# STM32F4Stick.net
KiCad netlist of a schematic drawn in EAGLE
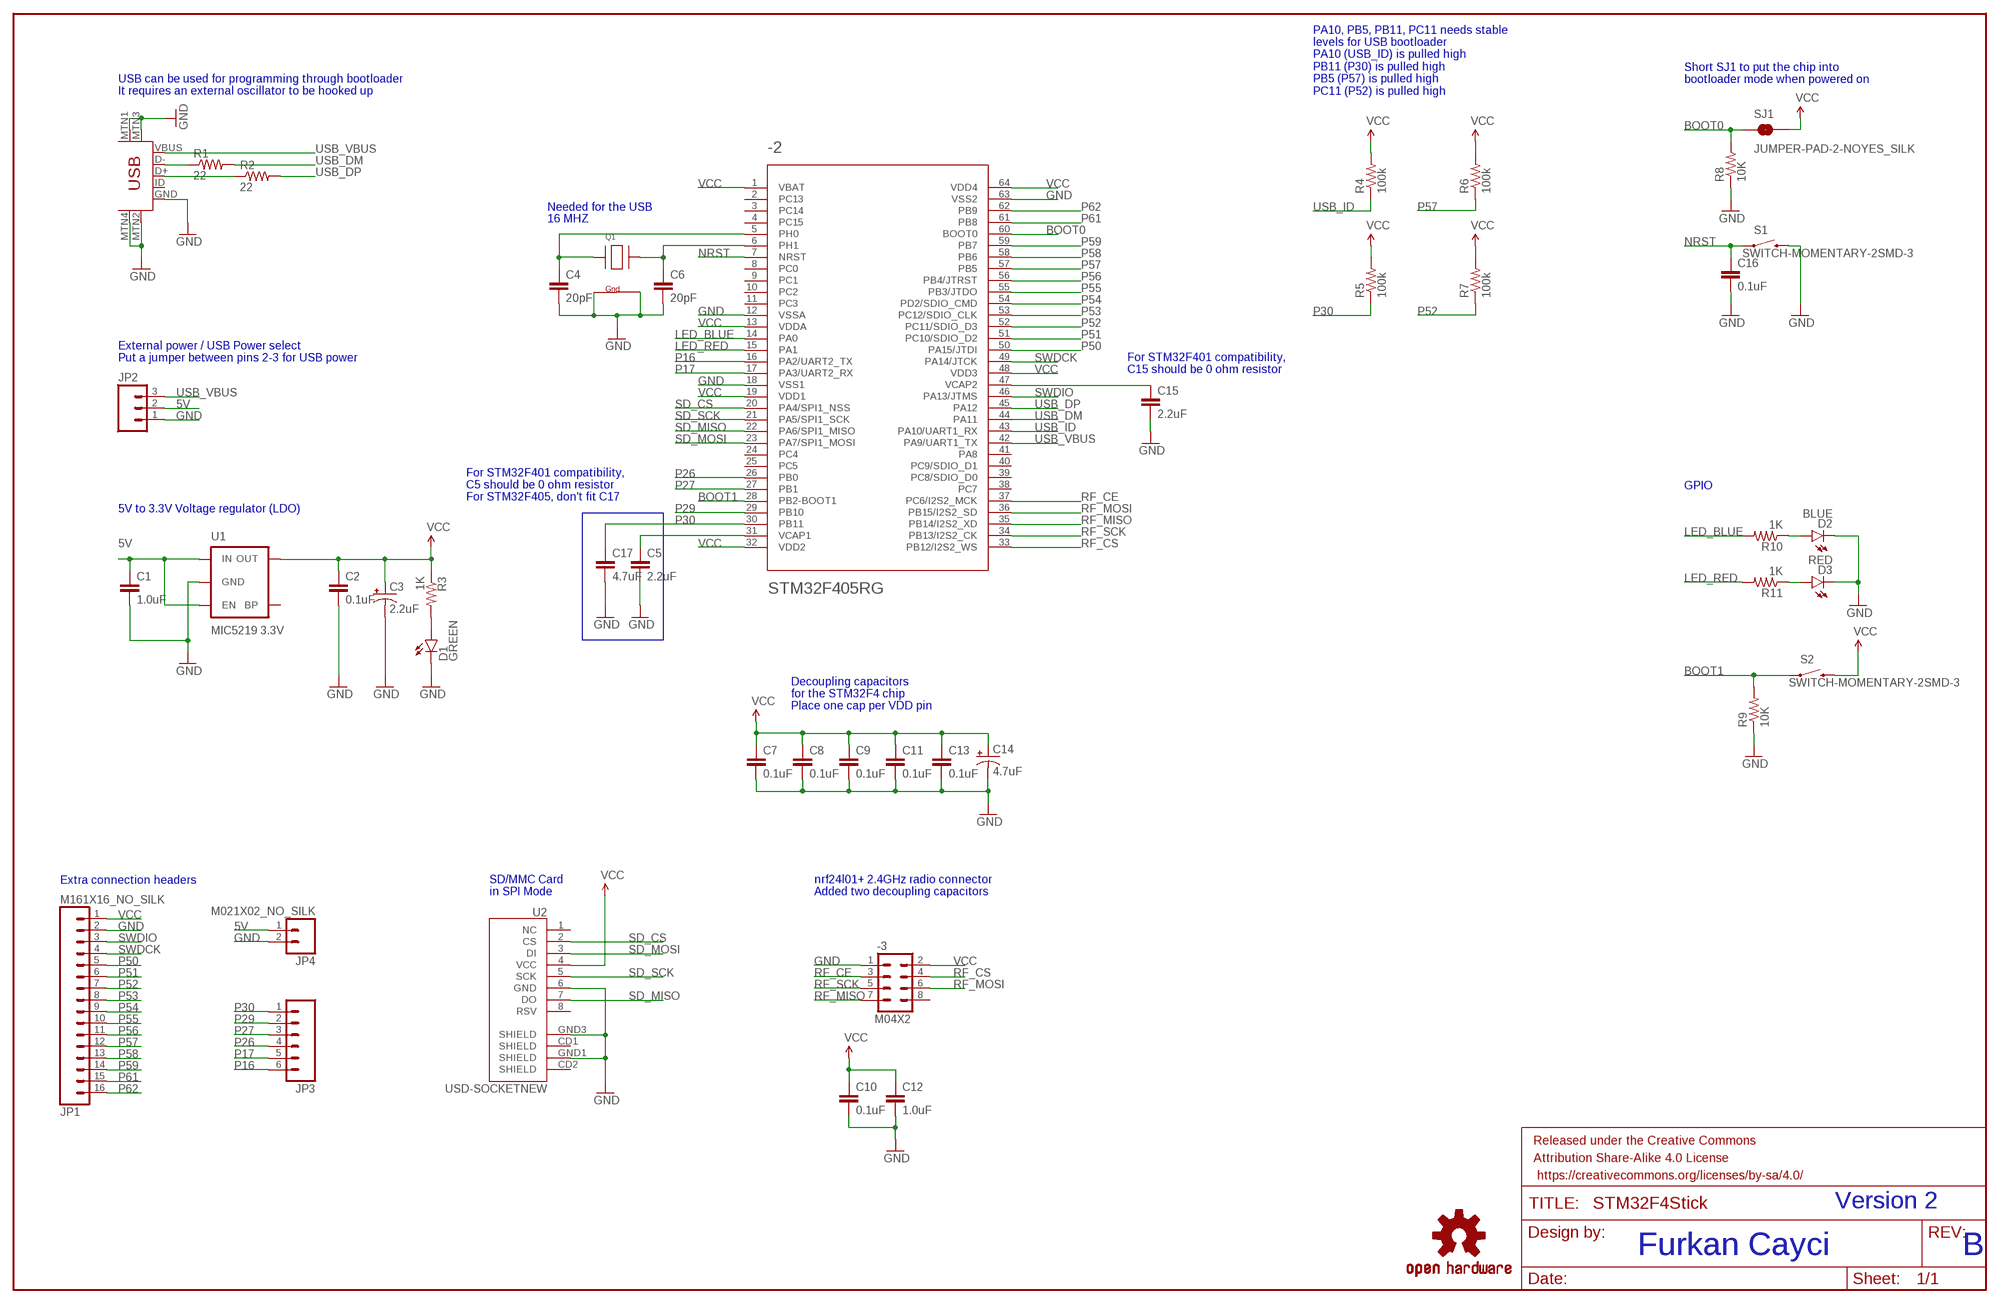
[diagram p0: schematic, sheet 1]

(export (version "E")
  (design (tool "Eeschema 10.0.6"))
  (components
    (comp (ref "-1")
      (value "USB-MINIB-5PIN")
      (footprint "eagle-import:USB-MINIB")
      (libsource (lib "eagle-import") (part "USB-MINIB-5PIN"))
    )
    (comp (ref "-2")
      (value "STM32F405RG")
      (footprint "eagle-import:TQFP64")
      (libsource (lib "eagle-import") (part "STM32F405RG"))
    )
    (comp (ref "-3")
      (value "M04X2")
      (footprint "eagle-import:2X4")
      (libsource (lib "eagle-import") (part "M04X2"))
    )
    (comp (ref "C1")
      (value "1.0uF")
      (footprint "eagle-import:0603-CAP")
      (libsource (lib "eagle-import") (part "1.0UF-16V-10%(0603)"))
    )
    (comp (ref "C2")
      (value "0.1uF")
      (footprint "eagle-import:0603-CAP")
      (libsource (lib "eagle-import") (part "0.1UF-25V-5%(0603)"))
    )
    (comp (ref "C3")
      (value "2.2uF")
      (footprint "eagle-import:EIA3216")
      (libsource (lib "eagle-import") (part "CAP_POL1206"))
    )
    (comp (ref "C4")
      (value "20pF")
      (footprint "eagle-import:0603-CAP")
      (libsource (lib "eagle-import") (part "12PF-50V-5%(0603)"))
    )
    (comp (ref "C5")
      (value "2.2uF")
      (footprint "eagle-import:0603-CAP")
      (libsource (lib "eagle-import") (part "2.2UF-10V-20%(0603)"))
    )
    (comp (ref "C6")
      (value "20pF")
      (footprint "eagle-import:0603-CAP")
      (libsource (lib "eagle-import") (part "12PF-50V-5%(0603)"))
    )
    (comp (ref "C7")
      (value "0.1uF")
      (footprint "eagle-import:0603-CAP")
      (libsource (lib "eagle-import") (part "0.1UF-25V-5%(0603)"))
    )
    (comp (ref "C8")
      (value "0.1uF")
      (footprint "eagle-import:0603-CAP")
      (libsource (lib "eagle-import") (part "0.1UF-25V-5%(0603)"))
    )
    (comp (ref "C9")
      (value "0.1uF")
      (footprint "eagle-import:0603-CAP")
      (libsource (lib "eagle-import") (part "0.1UF-25V-5%(0603)"))
    )
    (comp (ref "C10")
      (value "0.1uF")
      (footprint "eagle-import:0603-CAP")
      (libsource (lib "eagle-import") (part "0.1UF-25V-5%(0603)"))
    )
    (comp (ref "C11")
      (value "0.1uF")
      (footprint "eagle-import:0603-CAP")
      (libsource (lib "eagle-import") (part "0.1UF-25V-5%(0603)"))
    )
    (comp (ref "C12")
      (value "1.0uF")
      (footprint "eagle-import:0603-CAP")
      (libsource (lib "eagle-import") (part "1.0UF-16V-10%(0603)"))
    )
    (comp (ref "C13")
      (value "0.1uF")
      (footprint "eagle-import:0603-CAP")
      (libsource (lib "eagle-import") (part "0.1UF-25V-5%(0603)"))
    )
    (comp (ref "C14")
      (value "4.7uF")
      (footprint "eagle-import:EIA3216")
      (libsource (lib "eagle-import") (part "CAP_POL1206"))
    )
    (comp (ref "C15")
      (value "2.2uF")
      (footprint "eagle-import:0603-CAP")
      (libsource (lib "eagle-import") (part "2.2UF-10V-20%(0603)"))
    )
    (comp (ref "C16")
      (value "0.1uF")
      (footprint "eagle-import:0603-CAP")
      (libsource (lib "eagle-import") (part "0.1UF-25V-5%(0603)"))
    )
    (comp (ref "C17")
      (value "4.7uF")
      (footprint "eagle-import:0603-CAP")
      (libsource (lib "eagle-import") (part "4.7UF-6.3V-10%(0603)0603"))
    )
    (comp (ref "D1")
      (value "GREEN")
      (footprint "eagle-import:LED-0603")
      (libsource (lib "eagle-import") (part "LED-GREEN0603"))
    )
    (comp (ref "D2")
      (value "BLUE")
      (footprint "eagle-import:LED-0603")
      (libsource (lib "eagle-import") (part "LED-BLUE0603"))
    )
    (comp (ref "D3")
      (value "RED")
      (footprint "eagle-import:LED-0603")
      (libsource (lib "eagle-import") (part "LED-RED0603"))
    )
    (comp (ref "FRAME1")
      (value "FRAME-LEDGER")
      (footprint "eagle-import:CREATIVE_COMMONS")
      (libsource (lib "eagle-import") (part "FRAME-LEDGER"))
    )
    (comp (ref "JP1")
      (value "M161X16_NO_SILK")
      (footprint "eagle-import:1X16_NO_SILK")
      (libsource (lib "eagle-import") (part "M161X16_NO_SILK"))
    )
    (comp (ref "JP2")
      (value "M031X03_NO_SILK")
      (footprint "eagle-import:1X03_NO_SILK")
      (libsource (lib "eagle-import") (part "M031X03_NO_SILK"))
    )
    (comp (ref "JP3")
      (value "M06NO_SILK")
      (footprint "eagle-import:1X06_NO_SILK")
      (libsource (lib "eagle-import") (part "M06NO_SILK"))
    )
    (comp (ref "JP4")
      (value "M021X02_NO_SILK")
      (footprint "eagle-import:1X02_NO_SILK")
      (libsource (lib "eagle-import") (part "M021X02_NO_SILK"))
    )
    (comp (ref "LOGO1")
      (value "OSHW-LOGOM")
      (footprint "eagle-import:OSHW-LOGO-M")
      (libsource (lib "eagle-import") (part "OSHW-LOGOM"))
    )
    (comp (ref "Q1")
      (value "XTAL-4-3225")
      (footprint "eagle-import:NX3225")
      (libsource (lib "eagle-import") (part "XTAL-4-3225"))
    )
    (comp (ref "R1")
      (value "22")
      (footprint "eagle-import:0603-RES")
      (libsource (lib "eagle-import") (part "22OHM1/10W1%(0603)"))
    )
    (comp (ref "R2")
      (value "22")
      (footprint "eagle-import:0603-RES")
      (libsource (lib "eagle-import") (part "22OHM1/10W1%(0603)"))
    )
    (comp (ref "R3")
      (value "1K")
      (footprint "eagle-import:0603-RES")
      (libsource (lib "eagle-import") (part "1KOHM1/10W1%(0603)"))
    )
    (comp (ref "R4")
      (value "100k")
      (footprint "eagle-import:0603-RES")
      (libsource (lib "eagle-import") (part "100KOHM1/10W1%(0603)"))
    )
    (comp (ref "R5")
      (value "100k")
      (footprint "eagle-import:0603-RES")
      (libsource (lib "eagle-import") (part "100KOHM1/10W1%(0603)"))
    )
    (comp (ref "R6")
      (value "100k")
      (footprint "eagle-import:0603-RES")
      (libsource (lib "eagle-import") (part "100KOHM1/10W1%(0603)"))
    )
    (comp (ref "R7")
      (value "100k")
      (footprint "eagle-import:0603-RES")
      (libsource (lib "eagle-import") (part "100KOHM1/10W1%(0603)"))
    )
    (comp (ref "R8")
      (value "10K")
      (footprint "eagle-import:0603-RES")
      (libsource (lib "eagle-import") (part "10KOHM1/10W1%(0603)0603"))
    )
    (comp (ref "R9")
      (value "10K")
      (footprint "eagle-import:0603-RES")
      (libsource (lib "eagle-import") (part "10KOHM1/10W1%(0603)0603"))
    )
    (comp (ref "R10")
      (value "1K")
      (footprint "eagle-import:0603-RES")
      (libsource (lib "eagle-import") (part "1KOHM1/10W1%(0603)"))
    )
    (comp (ref "R11")
      (value "1K")
      (footprint "eagle-import:0603-RES")
      (libsource (lib "eagle-import") (part "1KOHM1/10W1%(0603)"))
    )
    (comp (ref "S1")
      (value "SWITCH-MOMENTARY-2SMD-3")
      (footprint "eagle-import:TACTILE_SWITCH_SMD-3")
      (libsource (lib "eagle-import") (part "SWITCH-MOMENTARY-2SMD-3"))
    )
    (comp (ref "S2")
      (value "SWITCH-MOMENTARY-2SMD-3")
      (footprint "eagle-import:TACTILE_SWITCH_SMD-3")
      (libsource (lib "eagle-import") (part "SWITCH-MOMENTARY-2SMD-3"))
    )
    (comp (ref "SJ1")
      (value "JUMPER-PAD-2-NOYES_SILK")
      (footprint "eagle-import:PAD-JUMPER-2-NO_YES_SILK")
      (libsource (lib "eagle-import") (part "JUMPER-PAD-2-NOYES_SILK"))
    )
    (comp (ref "U1")
      (value "MIC5219 3.3V")
      (footprint "eagle-import:SOT23-5")
      (libsource (lib "eagle-import") (part "V_REG_MIC52193.3V"))
    )
    (comp (ref "U2")
      (value "USD-SOCKETNEW")
      (footprint "eagle-import:MICRO-SD-SOCKET-PP")
      (libsource (lib "eagle-import") (part "USD-SOCKETNEW"))
    )
  )
  (nets
    (net (code "1") (name "/5V") (class "Default")
      (node (ref "C1") (pin "1") (pinfunction "1_1") (pintype "passive"))
      (node (ref "JP2") (pin "2") (pinfunction "2_2") (pintype "passive"))
      (node (ref "JP4") (pin "1") (pinfunction "1_1") (pintype "passive"))
      (node (ref "U1") (pin "1") (pinfunction "IN_1") (pintype "input"))
      (node (ref "U1") (pin "3") (pinfunction "EN_3") (pintype "input"))
    )
    (net (code "2") (name "/BOOT0") (class "Default")
      (node (ref "-2") (pin "60") (pinfunction "BOOT0_60") (pintype "bidirectional"))
      (node (ref "R8") (pin "2") (pinfunction "2_2") (pintype "passive"))
      (node (ref "SJ1") (pin "1") (pinfunction "1_1") (pintype "passive"))
    )
    (net (code "3") (name "/BOOT1") (class "Default")
      (node (ref "-2") (pin "28") (pinfunction "PB2-BOOT1_28") (pintype "bidirectional"))
      (node (ref "R9") (pin "2") (pinfunction "2_2") (pintype "passive"))
      (node (ref "S2") (pin "1") (pinfunction "1_1") (pintype "passive"))
    )
    (net (code "4") (name "/LED_BLUE") (class "Default")
      (node (ref "-2") (pin "14") (pinfunction "PA0_14") (pintype "bidirectional"))
      (node (ref "R10") (pin "2") (pinfunction "2_2") (pintype "passive"))
    )
    (net (code "5") (name "/LED_RED") (class "Default")
      (node (ref "-2") (pin "15") (pinfunction "PA1_15") (pintype "bidirectional"))
      (node (ref "R11") (pin "2") (pinfunction "2_2") (pintype "passive"))
    )
    (net (code "6") (name "/NRST") (class "Default")
      (node (ref "-2") (pin "7") (pinfunction "NRST_7") (pintype "bidirectional"))
      (node (ref "C16") (pin "1") (pinfunction "1_1") (pintype "passive"))
      (node (ref "S1") (pin "1") (pinfunction "1_1") (pintype "passive"))
    )
    (net (code "7") (name "/P16") (class "Default")
      (node (ref "-2") (pin "16") (pinfunction "PA2/UART2_TX_16") (pintype "bidirectional"))
      (node (ref "JP3") (pin "6") (pinfunction "6_6") (pintype "passive"))
    )
    (net (code "8") (name "/P17") (class "Default")
      (node (ref "-2") (pin "17") (pinfunction "PA3/UART2_RX_17") (pintype "bidirectional"))
      (node (ref "JP3") (pin "5") (pinfunction "5_5") (pintype "passive"))
    )
    (net (code "9") (name "/P26") (class "Default")
      (node (ref "-2") (pin "26") (pinfunction "PB0_26") (pintype "bidirectional"))
      (node (ref "JP3") (pin "4") (pinfunction "4_4") (pintype "passive"))
    )
    (net (code "10") (name "/P27") (class "Default")
      (node (ref "-2") (pin "27") (pinfunction "PB1_27") (pintype "bidirectional"))
      (node (ref "JP3") (pin "3") (pinfunction "3_3") (pintype "passive"))
    )
    (net (code "11") (name "/P29") (class "Default")
      (node (ref "-2") (pin "29") (pinfunction "PB10_29") (pintype "bidirectional"))
      (node (ref "JP3") (pin "2") (pinfunction "2_2") (pintype "passive"))
    )
    (net (code "12") (name "/P30") (class "Default")
      (node (ref "-2") (pin "30") (pinfunction "PB11_30") (pintype "bidirectional"))
      (node (ref "C17") (pin "1") (pinfunction "1_1") (pintype "passive"))
      (node (ref "JP3") (pin "1") (pinfunction "1_1") (pintype "passive"))
      (node (ref "R5") (pin "1") (pinfunction "1_1") (pintype "passive"))
    )
    (net (code "13") (name "/P50") (class "Default")
      (node (ref "-2") (pin "50") (pinfunction "PA15/JTDI_50") (pintype "bidirectional"))
      (node (ref "JP1") (pin "5") (pinfunction "5_5") (pintype "passive"))
    )
    (net (code "14") (name "/P51") (class "Default")
      (node (ref "-2") (pin "51") (pinfunction "PC10/SDIO_D2_51") (pintype "bidirectional"))
      (node (ref "JP1") (pin "6") (pinfunction "6_6") (pintype "passive"))
    )
    (net (code "15") (name "/P52") (class "Default")
      (node (ref "-2") (pin "52") (pinfunction "PC11/SDIO_D3_52") (pintype "bidirectional"))
      (node (ref "JP1") (pin "7") (pinfunction "7_7") (pintype "passive"))
      (node (ref "R7") (pin "1") (pinfunction "1_1") (pintype "passive"))
    )
    (net (code "16") (name "/P53") (class "Default")
      (node (ref "-2") (pin "53") (pinfunction "PC12/SDIO_CLK_53") (pintype "bidirectional"))
      (node (ref "JP1") (pin "8") (pinfunction "8_8") (pintype "passive"))
    )
    (net (code "17") (name "/P54") (class "Default")
      (node (ref "-2") (pin "54") (pinfunction "PD2/SDIO_CMD_54") (pintype "bidirectional"))
      (node (ref "JP1") (pin "9") (pinfunction "9_9") (pintype "passive"))
    )
    (net (code "18") (name "/P55") (class "Default")
      (node (ref "-2") (pin "55") (pinfunction "PB3/JTDO_55") (pintype "bidirectional"))
      (node (ref "JP1") (pin "10") (pinfunction "10_10") (pintype "passive"))
    )
    (net (code "19") (name "/P56") (class "Default")
      (node (ref "-2") (pin "56") (pinfunction "PB4/JTRST_56") (pintype "bidirectional"))
      (node (ref "JP1") (pin "11") (pinfunction "11_11") (pintype "passive"))
    )
    (net (code "20") (name "/P57") (class "Default")
      (node (ref "-2") (pin "57") (pinfunction "PB5_57") (pintype "bidirectional"))
      (node (ref "JP1") (pin "12") (pinfunction "12_12") (pintype "passive"))
      (node (ref "R6") (pin "1") (pinfunction "1_1") (pintype "passive"))
    )
    (net (code "21") (name "/P58") (class "Default")
      (node (ref "-2") (pin "58") (pinfunction "PB6_58") (pintype "bidirectional"))
      (node (ref "JP1") (pin "13") (pinfunction "13_13") (pintype "passive"))
    )
    (net (code "22") (name "/P59") (class "Default")
      (node (ref "-2") (pin "59") (pinfunction "PB7_59") (pintype "bidirectional"))
      (node (ref "JP1") (pin "14") (pinfunction "14_14") (pintype "passive"))
    )
    (net (code "23") (name "/P61") (class "Default")
      (node (ref "-2") (pin "61") (pinfunction "PB8_61") (pintype "bidirectional"))
      (node (ref "JP1") (pin "15") (pinfunction "15_15") (pintype "passive"))
    )
    (net (code "24") (name "/P62") (class "Default")
      (node (ref "-2") (pin "62") (pinfunction "PB9_62") (pintype "bidirectional"))
      (node (ref "JP1") (pin "16") (pinfunction "16_16") (pintype "passive"))
    )
    (net (code "25") (name "/RF_CE") (class "Default")
      (node (ref "-2") (pin "37") (pinfunction "PC6/I2S2_MCK_37") (pintype "bidirectional"))
      (node (ref "-3") (pin "3") (pinfunction "3_3") (pintype "passive"))
    )
    (net (code "26") (name "/RF_CS") (class "Default")
      (node (ref "-2") (pin "33") (pinfunction "PB12/I2S2_WS_33") (pintype "bidirectional"))
      (node (ref "-3") (pin "4") (pinfunction "4_4") (pintype "passive"))
    )
    (net (code "27") (name "/RF_MISO") (class "Default")
      (node (ref "-2") (pin "35") (pinfunction "PB14/I2S2_XD_35") (pintype "bidirectional"))
      (node (ref "-3") (pin "7") (pinfunction "7_7") (pintype "passive"))
    )
    (net (code "28") (name "/RF_MOSI") (class "Default")
      (node (ref "-2") (pin "36") (pinfunction "PB15/I2S2_SD_36") (pintype "bidirectional"))
      (node (ref "-3") (pin "6") (pinfunction "6_6") (pintype "passive"))
    )
    (net (code "29") (name "/RF_SCK") (class "Default")
      (node (ref "-2") (pin "34") (pinfunction "PB13/I2S2_CK_34") (pintype "bidirectional"))
      (node (ref "-3") (pin "5") (pinfunction "5_5") (pintype "passive"))
    )
    (net (code "30") (name "/SD_CS") (class "Default")
      (node (ref "-2") (pin "20") (pinfunction "PA4/SPI1_NSS_20") (pintype "bidirectional"))
      (node (ref "U2") (pin "2") (pinfunction "CS_2") (pintype "bidirectional"))
    )
    (net (code "31") (name "/SD_MISO") (class "Default")
      (node (ref "-2") (pin "22") (pinfunction "PA6/SPI1_MISO_22") (pintype "bidirectional"))
      (node (ref "U2") (pin "7") (pinfunction "DO_7") (pintype "bidirectional"))
    )
    (net (code "32") (name "/SD_MOSI") (class "Default")
      (node (ref "-2") (pin "23") (pinfunction "PA7/SPI1_MOSI_23") (pintype "bidirectional"))
      (node (ref "U2") (pin "3") (pinfunction "DI_3") (pintype "bidirectional"))
    )
    (net (code "33") (name "/SD_SCK") (class "Default")
      (node (ref "-2") (pin "21") (pinfunction "PA5/SPI1_SCK_21") (pintype "bidirectional"))
      (node (ref "U2") (pin "5") (pinfunction "SCK_5") (pintype "bidirectional"))
    )
    (net (code "34") (name "/SWDCK") (class "Default")
      (node (ref "-2") (pin "49") (pinfunction "PA14/JTCK_49") (pintype "bidirectional"))
      (node (ref "JP1") (pin "4") (pinfunction "4_4") (pintype "passive"))
    )
    (net (code "35") (name "/SWDIO") (class "Default")
      (node (ref "-2") (pin "46") (pinfunction "PA13/JTMS_46") (pintype "bidirectional"))
      (node (ref "JP1") (pin "3") (pinfunction "3_3") (pintype "passive"))
    )
    (net (code "36") (name "/USB_DM") (class "Default")
      (node (ref "-2") (pin "44") (pinfunction "PA11_44") (pintype "bidirectional"))
      (node (ref "R1") (pin "2") (pinfunction "2_2") (pintype "passive"))
    )
    (net (code "37") (name "/USB_DP") (class "Default")
      (node (ref "-2") (pin "45") (pinfunction "PA12_45") (pintype "bidirectional"))
      (node (ref "R2") (pin "2") (pinfunction "2_2") (pintype "passive"))
    )
    (net (code "38") (name "/USB_ID") (class "Default")
      (node (ref "-2") (pin "43") (pinfunction "PA10/UART1_RX_43") (pintype "bidirectional"))
      (node (ref "R4") (pin "1") (pinfunction "1_1") (pintype "passive"))
    )
    (net (code "39") (name "/USB_VBUS") (class "Default")
      (node (ref "-1") (pin "VBUS") (pinfunction "VBUS_VBUS") (pintype "bidirectional"))
      (node (ref "-2") (pin "42") (pinfunction "PA9/UART1_TX_42") (pintype "bidirectional"))
      (node (ref "JP2") (pin "3") (pinfunction "3_3") (pintype "passive"))
    )
    (net (code "40") (name "GND") (class "Default")
      (node (ref "-1") (pin "GND") (pinfunction "GND_GND") (pintype "bidirectional"))
      (node (ref "-1") (pin "MTN1") (pinfunction "MTN2_MTN1") (pintype "bidirectional"))
      (node (ref "-1") (pin "MTN2") (pinfunction "MTN3_MTN2") (pintype "bidirectional"))
      (node (ref "-1") (pin "MTN3") (pinfunction "MTN1_MTN3") (pintype "bidirectional"))
      (node (ref "-1") (pin "MTN4") (pinfunction "MTN4_MTN4") (pintype "bidirectional"))
      (node (ref "-2") (pin "12") (pinfunction "VSSA_12") (pintype "bidirectional"))
      (node (ref "-2") (pin "18") (pinfunction "VSS1_18") (pintype "bidirectional"))
      (node (ref "-2") (pin "63") (pinfunction "VSS2_63") (pintype "bidirectional"))
      (node (ref "-3") (pin "1") (pinfunction "1_1") (pintype "passive"))
      (node (ref "C1") (pin "2") (pinfunction "2_2") (pintype "passive"))
      (node (ref "C10") (pin "2") (pinfunction "2_2") (pintype "passive"))
      (node (ref "C11") (pin "2") (pinfunction "2_2") (pintype "passive"))
      (node (ref "C12") (pin "2") (pinfunction "2_2") (pintype "passive"))
      (node (ref "C13") (pin "2") (pinfunction "2_2") (pintype "passive"))
      (node (ref "C14") (pin "C") (pinfunction "-_C") (pintype "passive"))
      (node (ref "C15") (pin "2") (pinfunction "2_2") (pintype "passive"))
      (node (ref "C16") (pin "2") (pinfunction "2_2") (pintype "passive"))
      (node (ref "C17") (pin "2") (pinfunction "2_2") (pintype "passive"))
      (node (ref "C2") (pin "2") (pinfunction "2_2") (pintype "passive"))
      (node (ref "C3") (pin "C") (pinfunction "-_C") (pintype "passive"))
      (node (ref "C4") (pin "2") (pinfunction "2_2") (pintype "passive"))
      (node (ref "C5") (pin "2") (pinfunction "2_2") (pintype "passive"))
      (node (ref "C6") (pin "2") (pinfunction "2_2") (pintype "passive"))
      (node (ref "C7") (pin "2") (pinfunction "2_2") (pintype "passive"))
      (node (ref "C8") (pin "2") (pinfunction "2_2") (pintype "passive"))
      (node (ref "C9") (pin "2") (pinfunction "2_2") (pintype "passive"))
      (node (ref "D1") (pin "C") (pinfunction "C_C") (pintype "passive"))
      (node (ref "D2") (pin "C") (pinfunction "C_C") (pintype "passive"))
      (node (ref "D3") (pin "C") (pinfunction "C_C") (pintype "passive"))
      (node (ref "JP1") (pin "2") (pinfunction "2_2") (pintype "passive"))
      (node (ref "JP2") (pin "1") (pinfunction "1_1") (pintype "passive"))
      (node (ref "JP4") (pin "2") (pinfunction "2_2") (pintype "passive"))
      (node (ref "Q1") (pin "2") (pinfunction "G2_2") (pintype "power_in"))
      (node (ref "Q1") (pin "4") (pinfunction "G1_4") (pintype "power_in"))
      (node (ref "R8") (pin "1") (pinfunction "1_1") (pintype "passive"))
      (node (ref "R9") (pin "1") (pinfunction "1_1") (pintype "passive"))
      (node (ref "S1") (pin "4") (pinfunction "2_4") (pintype "passive"))
      (node (ref "U1") (pin "2") (pinfunction "GND_2") (pintype "input"))
      (node (ref "U2") (pin "6") (pinfunction "GND_6") (pintype "bidirectional"))
      (node (ref "U2") (pin "GND1") (pinfunction "SHIELD_GND1") (pintype "bidirectional"))
      (node (ref "U2") (pin "GND3") (pinfunction "SHIELD_GND3") (pintype "bidirectional"))
    )
    (net (code "41") (name "Net-(-1-PadD+)") (class "Default")
      (node (ref "-1") (pin "D+") (pinfunction "D+_D+") (pintype "bidirectional"))
      (node (ref "R2") (pin "1") (pinfunction "1_1") (pintype "passive"))
    )
    (net (code "42") (name "Net-(-1-PadD-)") (class "Default")
      (node (ref "-1") (pin "D-") (pinfunction "D-_D-") (pintype "bidirectional"))
      (node (ref "R1") (pin "1") (pinfunction "1_1") (pintype "passive"))
    )
    (net (code "43") (name "Net-(-2-PH0)") (class "Default")
      (node (ref "-2") (pin "5") (pinfunction "PH0_5") (pintype "bidirectional"))
      (node (ref "C4") (pin "1") (pinfunction "1_1") (pintype "passive"))
      (node (ref "Q1") (pin "1") (pinfunction "X1_1") (pintype "bidirectional"))
    )
    (net (code "44") (name "Net-(-2-PH1)") (class "Default")
      (node (ref "-2") (pin "6") (pinfunction "PH1_6") (pintype "bidirectional"))
      (node (ref "C6") (pin "1") (pinfunction "1_1") (pintype "passive"))
      (node (ref "Q1") (pin "3") (pinfunction "X2_3") (pintype "bidirectional"))
    )
    (net (code "45") (name "Net-(-2-VCAP1)") (class "Default")
      (node (ref "-2") (pin "31") (pinfunction "VCAP1_31") (pintype "bidirectional"))
      (node (ref "C5") (pin "1") (pinfunction "1_1") (pintype "passive"))
    )
    (net (code "46") (name "Net-(-2-VCAP2)") (class "Default")
      (node (ref "-2") (pin "47") (pinfunction "VCAP2_47") (pintype "bidirectional"))
      (node (ref "C15") (pin "1") (pinfunction "1_1") (pintype "passive"))
    )
    (net (code "47") (name "Net-(D1-PadA)") (class "Default")
      (node (ref "D1") (pin "A") (pinfunction "A_A") (pintype "passive"))
      (node (ref "R3") (pin "2") (pinfunction "2_2") (pintype "passive"))
    )
    (net (code "48") (name "Net-(D2-PadA)") (class "Default")
      (node (ref "D2") (pin "A") (pinfunction "A_A") (pintype "passive"))
      (node (ref "R10") (pin "1") (pinfunction "1_1") (pintype "passive"))
    )
    (net (code "49") (name "Net-(D3-PadA)") (class "Default")
      (node (ref "D3") (pin "A") (pinfunction "A_A") (pintype "passive"))
      (node (ref "R11") (pin "1") (pinfunction "1_1") (pintype "passive"))
    )
    (net (code "50") (name "VCC") (class "Default")
      (node (ref "-2") (pin "1") (pinfunction "VBAT_1") (pintype "bidirectional"))
      (node (ref "-2") (pin "13") (pinfunction "VDDA_13") (pintype "bidirectional"))
      (node (ref "-2") (pin "19") (pinfunction "VDD1_19") (pintype "bidirectional"))
      (node (ref "-2") (pin "32") (pinfunction "VDD2_32") (pintype "bidirectional"))
      (node (ref "-2") (pin "48") (pinfunction "VDD3_48") (pintype "bidirectional"))
      (node (ref "-2") (pin "64") (pinfunction "VDD4_64") (pintype "bidirectional"))
      (node (ref "-3") (pin "2") (pinfunction "2_2") (pintype "passive"))
      (node (ref "C10") (pin "1") (pinfunction "1_1") (pintype "passive"))
      (node (ref "C11") (pin "1") (pinfunction "1_1") (pintype "passive"))
      (node (ref "C12") (pin "1") (pinfunction "1_1") (pintype "passive"))
      (node (ref "C13") (pin "1") (pinfunction "1_1") (pintype "passive"))
      (node (ref "C14") (pin "A") (pinfunction "+_A") (pintype "passive"))
      (node (ref "C2") (pin "1") (pinfunction "1_1") (pintype "passive"))
      (node (ref "C3") (pin "A") (pinfunction "+_A") (pintype "passive"))
      (node (ref "C7") (pin "1") (pinfunction "1_1") (pintype "passive"))
      (node (ref "C8") (pin "1") (pinfunction "1_1") (pintype "passive"))
      (node (ref "C9") (pin "1") (pinfunction "1_1") (pintype "passive"))
      (node (ref "JP1") (pin "1") (pinfunction "1_1") (pintype "passive"))
      (node (ref "R3") (pin "1") (pinfunction "1_1") (pintype "passive"))
      (node (ref "R4") (pin "2") (pinfunction "2_2") (pintype "passive"))
      (node (ref "R5") (pin "2") (pinfunction "2_2") (pintype "passive"))
      (node (ref "R6") (pin "2") (pinfunction "2_2") (pintype "passive"))
      (node (ref "R7") (pin "2") (pinfunction "2_2") (pintype "passive"))
      (node (ref "S2") (pin "4") (pinfunction "2_4") (pintype "passive"))
      (node (ref "SJ1") (pin "2") (pinfunction "2_2") (pintype "passive"))
      (node (ref "U1") (pin "5") (pinfunction "OUT_5") (pintype "passive"))
      (node (ref "U2") (pin "4") (pinfunction "VCC_4") (pintype "bidirectional"))
    )
    (net (code "51") (name "unconnected-(-1-PadID)") (class "Default")
      (node (ref "-1") (pin "ID") (pinfunction "ID_ID") (pintype "bidirectional"))
    )
    (net (code "52") (name "unconnected-(-2-PA8-Pad41)") (class "Default")
      (node (ref "-2") (pin "41") (pinfunction "PA8_41") (pintype "bidirectional"))
    )
    (net (code "53") (name "unconnected-(-2-PC0-Pad8)") (class "Default")
      (node (ref "-2") (pin "8") (pinfunction "PC0_8") (pintype "bidirectional"))
    )
    (net (code "54") (name "unconnected-(-2-PC1-Pad9)") (class "Default")
      (node (ref "-2") (pin "9") (pinfunction "PC1_9") (pintype "bidirectional"))
    )
    (net (code "55") (name "unconnected-(-2-PC2-Pad10)") (class "Default")
      (node (ref "-2") (pin "10") (pinfunction "PC2_10") (pintype "bidirectional"))
    )
    (net (code "56") (name "unconnected-(-2-PC3-Pad11)") (class "Default")
      (node (ref "-2") (pin "11") (pinfunction "PC3_11") (pintype "bidirectional"))
    )
    (net (code "57") (name "unconnected-(-2-PC4-Pad24)") (class "Default")
      (node (ref "-2") (pin "24") (pinfunction "PC4_24") (pintype "bidirectional"))
    )
    (net (code "58") (name "unconnected-(-2-PC5-Pad25)") (class "Default")
      (node (ref "-2") (pin "25") (pinfunction "PC5_25") (pintype "bidirectional"))
    )
    (net (code "59") (name "unconnected-(-2-PC7-Pad38)") (class "Default")
      (node (ref "-2") (pin "38") (pinfunction "PC7_38") (pintype "bidirectional"))
    )
    (net (code "60") (name "unconnected-(-2-PC8{slash}SDIO_D0-Pad39)") (class "Default")
      (node (ref "-2") (pin "39") (pinfunction "PC8/SDIO_D0_39") (pintype "bidirectional"))
    )
    (net (code "61") (name "unconnected-(-2-PC9{slash}SDIO_D1-Pad40)") (class "Default")
      (node (ref "-2") (pin "40") (pinfunction "PC9/SDIO_D1_40") (pintype "bidirectional"))
    )
    (net (code "62") (name "unconnected-(-2-PC13-Pad2)") (class "Default")
      (node (ref "-2") (pin "2") (pinfunction "PC13_2") (pintype "bidirectional"))
    )
    (net (code "63") (name "unconnected-(-2-PC14-Pad3)") (class "Default")
      (node (ref "-2") (pin "3") (pinfunction "PC14_3") (pintype "bidirectional"))
    )
    (net (code "64") (name "unconnected-(-2-PC15-Pad4)") (class "Default")
      (node (ref "-2") (pin "4") (pinfunction "PC15_4") (pintype "bidirectional"))
    )
    (net (code "65") (name "unconnected-(-3-Pad8)") (class "Default")
      (node (ref "-3") (pin "8") (pinfunction "8_8") (pintype "passive"))
    )
    (net (code "66") (name "unconnected-(U1-BP-Pad4)") (class "Default")
      (node (ref "U1") (pin "4") (pinfunction "BP_4") (pintype "input"))
    )
    (net (code "67") (name "unconnected-(U2-NC-Pad1)") (class "Default")
      (node (ref "U2") (pin "1") (pinfunction "NC_1") (pintype "bidirectional"))
    )
    (net (code "68") (name "unconnected-(U2-RSV-Pad8)") (class "Default")
      (node (ref "U2") (pin "8") (pinfunction "RSV_8") (pintype "bidirectional"))
    )
    (net (code "69") (name "unconnected-(U2-SHIELD-PadCD1)") (class "Default")
      (node (ref "U2") (pin "CD1") (pinfunction "SHIELD_CD1") (pintype "bidirectional"))
    )
    (net (code "70") (name "unconnected-(U2-SHIELD-PadCD2)") (class "Default")
      (node (ref "U2") (pin "CD2") (pinfunction "SHIELD_CD2") (pintype "bidirectional"))
    )
  )
)
